# Connectors.net
KiCad netlist of a schematic drawn in Altium Designer
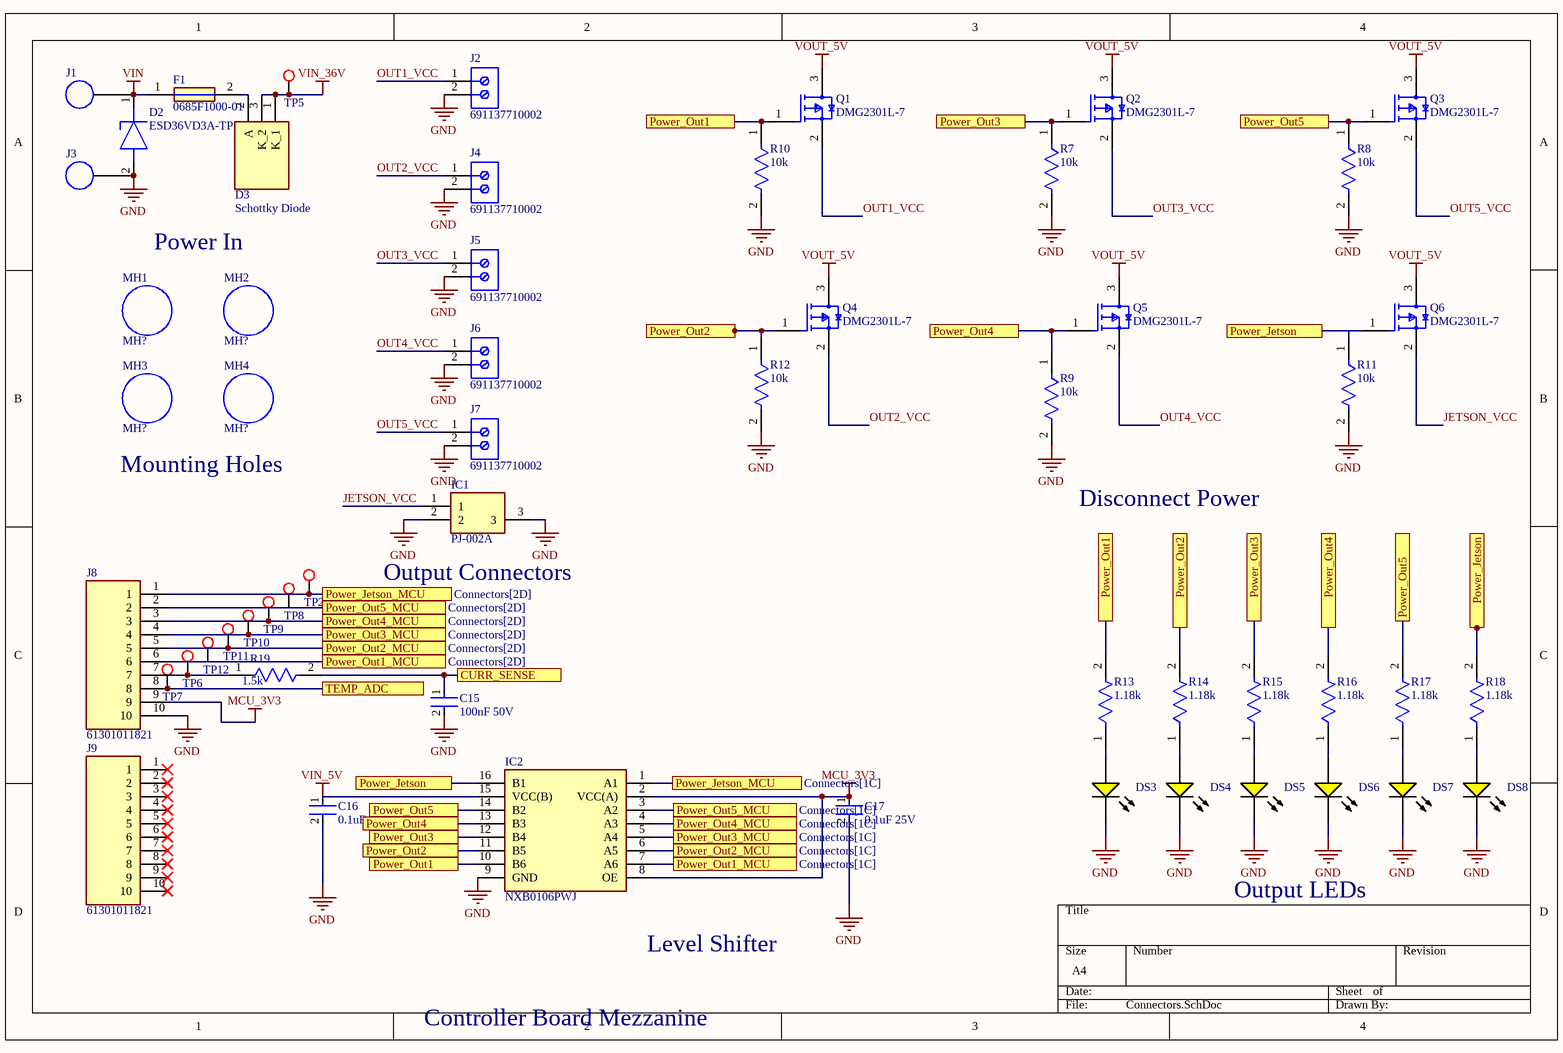
[diagram p0: Connectors.SchDoc]

(export (version "E")
  (design (tool "Eeschema 10.0.6"))
  (components
    (comp (ref "C15")
      (value "100nF 50V")
      (footprint "FP-CL31-IPC_C")
      (description "Cap Ceramic 100nF 50V X7R ±10% SMD 1206 +125°C Embossed T/R")
      (fields (field (name "TOLERANCE") "10%"))
      (libsource (lib "Altium Content Vault") (part "b4654b650e69147ec39a6b967a45e02"))
    )
    (comp (ref "C16")
      (value "0.1uF 25V")
      (footprint "FP-CL21-IPC_C")
      (description "CL21 Series 0805 100nF 25V -20/+80% Tolerance Y5V Multilayer Ceramic Chip Capacitor")
      (fields (field (name "TOLERANCE") "80%"))
      (libsource (lib "Altium Content Vault") (part "b4654b650e69147ec39a6b967a45e02"))
    )
    (comp (ref "C17")
      (value "0.1uF 25V")
      (footprint "FP-CL21-IPC_C")
      (description "CL21 Series 0805 100nF 25V -20/+80% Tolerance Y5V Multilayer Ceramic Chip Capacitor")
      (fields (field (name "TOLERANCE") "80%"))
      (libsource (lib "Altium Content Vault") (part "b4654b650e69147ec39a6b967a45e02"))
    )
    (comp (ref "D2")
      (value "ESD36VD3A-TP")
      (footprint "SamacSys:SOD2512X115N")
      (description "Diode ESD (Uni-directional)")
      (libsource (lib "*") (part "ESD36VD3A-TP"))
    )
    (comp (ref "D3")
      (value "Schottky Diode")
      (footprint "SamacSys:PMEG4010EXEX")
      (fields (field (name "MANUFACTURER_PART_NUMBER") "PMEG6010EXEX"))
      (libsource (lib "*") (part "PMEG6010EXEX"))
    )
    (comp (ref "DS3")
      (value "HSMY-C190")
      (footprint "AVAG-HSMX-C190_V")
      (description "LED Uni-Color Yellow, 65 mW, 20 mA, -40 to 85 degC, 2-Pin SMD, RoHS, Tape and Reel")
      (fields (field (name "TOLERANCE") "1%"))
      (libsource (lib "Altium Content Vault") (part "LED-YELLOW-AK-2"))
    )
    (comp (ref "DS4")
      (value "HSMY-C190")
      (footprint "AVAG-HSMX-C190_V")
      (description "LED Uni-Color Yellow, 65 mW, 20 mA, -40 to 85 degC, 2-Pin SMD, RoHS, Tape and Reel")
      (fields (field (name "TOLERANCE") "1%"))
      (libsource (lib "Altium Content Vault") (part "LED-YELLOW-AK-2"))
    )
    (comp (ref "DS5")
      (value "HSMY-C190")
      (footprint "AVAG-HSMX-C190_V")
      (description "LED Uni-Color Yellow, 65 mW, 20 mA, -40 to 85 degC, 2-Pin SMD, RoHS, Tape and Reel")
      (fields (field (name "TOLERANCE") "1%"))
      (libsource (lib "Altium Content Vault") (part "LED-YELLOW-AK-2"))
    )
    (comp (ref "DS6")
      (value "HSMY-C190")
      (footprint "AVAG-HSMX-C190_V")
      (description "LED Uni-Color Yellow, 65 mW, 20 mA, -40 to 85 degC, 2-Pin SMD, RoHS, Tape and Reel")
      (fields (field (name "TOLERANCE") "1%"))
      (libsource (lib "Altium Content Vault") (part "LED-YELLOW-AK-2"))
    )
    (comp (ref "DS7")
      (value "HSMY-C190")
      (footprint "AVAG-HSMX-C190_V")
      (description "LED Uni-Color Yellow, 65 mW, 20 mA, -40 to 85 degC, 2-Pin SMD, RoHS, Tape and Reel")
      (fields (field (name "TOLERANCE") "1%"))
      (libsource (lib "Altium Content Vault") (part "LED-YELLOW-AK-2"))
    )
    (comp (ref "DS8")
      (value "HSMY-C190")
      (footprint "AVAG-HSMX-C190_V")
      (description "LED Uni-Color Yellow, 65 mW, 20 mA, -40 to 85 degC, 2-Pin SMD, RoHS, Tape and Reel")
      (fields (field (name "TOLERANCE") "1%"))
      (libsource (lib "Altium Content Vault") (part "LED-YELLOW-AK-2"))
    )
    (comp (ref "F1")
      (value "0685F1000-01")
      (footprint "SamacSys:FUSC3216X83N")
      (description "Fuse")
      (libsource (lib "*") (part "0685F1000-01"))
    )
    (comp (ref "IC1")
      (value "PJ-002A")
      (footprint "SamacSys:PJ002A")
      (description "Integrated Circuit")
      (fields (field (name "MOUSER PART NUMBER") "490-PJ-002A"))
      (libsource (lib "*") (part "PJ-002A"))
    )
    (comp (ref "IC2")
      (value "NXB0106PWJ")
      (footprint "SamacSys:SOP65P640X110-16N")
      (description "Integrated Circuit")
      (fields (field (name "MOUSER PART NUMBER") "771-NXB0106PWJ"))
      (libsource (lib "*") (part "NXB0106PWJ"))
    )
    (comp (ref "J1")
      (value "J?")
      (footprint "Power Screw Terminal")
      (libsource (lib "Schlib1") (part "Screw Connector"))
    )
    (comp (ref "J2")
      (value "691137710002")
      (footprint "691137710002")
      (libsource (lib "Altium Content Vault") (part "TBL - 1R - 02P - Screw"))
    )
    (comp (ref "J3")
      (value "J?")
      (footprint "Power Screw Terminal")
      (libsource (lib "Schlib1") (part "Screw Connector"))
    )
    (comp (ref "J4")
      (value "691137710002")
      (footprint "691137710002")
      (libsource (lib "Altium Content Vault") (part "TBL - 1R - 02P - Screw"))
    )
    (comp (ref "J5")
      (value "691137710002")
      (footprint "691137710002")
      (libsource (lib "Altium Content Vault") (part "TBL - 1R - 02P - Screw"))
    )
    (comp (ref "J6")
      (value "691137710002")
      (footprint "691137710002")
      (libsource (lib "Altium Content Vault") (part "TBL - 1R - 02P - Screw"))
    )
    (comp (ref "J7")
      (value "691137710002")
      (footprint "691137710002")
      (libsource (lib "Altium Content Vault") (part "TBL - 1R - 02P - Screw"))
    )
    (comp (ref "J8")
      (value "61301011821")
      (footprint "SamacSys:RHDR10W60P0X254_1X10_2590X250X850P")
      (description "Connector")
      (fields (field (name "MOUSER PART NUMBER") "710-61301011821"))
      (libsource (lib "*") (part "61301011821"))
    )
    (comp (ref "J9")
      (value "61301011821")
      (footprint "SamacSys:RHDR10W60P0X254_1X10_2590X250X850P")
      (description "Connector")
      (fields (field (name "MOUSER PART NUMBER") "710-61301011821"))
      (libsource (lib "*") (part "61301011821"))
    )
    (comp (ref "MH1")
      (value "MH?")
      (footprint "Mounting Hole")
      (libsource (lib "Schlib1") (part "Mounting Hole"))
    )
    (comp (ref "MH2")
      (value "MH?")
      (footprint "Mounting Hole")
      (libsource (lib "Schlib1") (part "Mounting Hole"))
    )
    (comp (ref "MH3")
      (value "MH?")
      (footprint "Mounting Hole")
      (libsource (lib "Schlib1") (part "Mounting Hole"))
    )
    (comp (ref "MH4")
      (value "MH?")
      (footprint "Mounting Hole")
      (libsource (lib "Schlib1") (part "Mounting Hole"))
    )
    (comp (ref "Q1")
      (value "DMG2301L-7")
      (footprint "FP-SOT23-MFG")
      (description "MOSFET P-CH 20V 3A SOT23")
      (fields
        (field (name "MANUFACTURER") "Diodes Inc.")
        (field (name "OCTOPART") "https://octopart.com/dmg2301l-7-diodes+inc.-67250456")
      )
      (libsource (lib "Altium Content Vault") (part "b8f99f9e586195791e7fb11725ebaeb"))
    )
    (comp (ref "Q2")
      (value "DMG2301L-7")
      (footprint "FP-SOT23-MFG")
      (description "MOSFET P-CH 20V 3A SOT23")
      (fields
        (field (name "MANUFACTURER") "Diodes Inc.")
        (field (name "OCTOPART") "https://octopart.com/dmg2301l-7-diodes+inc.-67250456")
      )
      (libsource (lib "Altium Content Vault") (part "b8f99f9e586195791e7fb11725ebaeb"))
    )
    (comp (ref "Q3")
      (value "DMG2301L-7")
      (footprint "FP-SOT23-MFG")
      (description "MOSFET P-CH 20V 3A SOT23")
      (fields
        (field (name "MANUFACTURER") "Diodes Inc.")
        (field (name "OCTOPART") "https://octopart.com/dmg2301l-7-diodes+inc.-67250456")
      )
      (libsource (lib "Altium Content Vault") (part "b8f99f9e586195791e7fb11725ebaeb"))
    )
    (comp (ref "Q4")
      (value "DMG2301L-7")
      (footprint "FP-SOT23-MFG")
      (description "MOSFET P-CH 20V 3A SOT23")
      (fields
        (field (name "MANUFACTURER") "Diodes Inc.")
        (field (name "OCTOPART") "https://octopart.com/dmg2301l-7-diodes+inc.-67250456")
      )
      (libsource (lib "Altium Content Vault") (part "b8f99f9e586195791e7fb11725ebaeb"))
    )
    (comp (ref "Q5")
      (value "DMG2301L-7")
      (footprint "FP-SOT23-MFG")
      (description "MOSFET P-CH 20V 3A SOT23")
      (fields
        (field (name "MANUFACTURER") "Diodes Inc.")
        (field (name "OCTOPART") "https://octopart.com/dmg2301l-7-diodes+inc.-67250456")
      )
      (libsource (lib "Altium Content Vault") (part "b8f99f9e586195791e7fb11725ebaeb"))
    )
    (comp (ref "Q6")
      (value "DMG2301L-7")
      (footprint "FP-SOT23-MFG")
      (description "MOSFET P-CH 20V 3A SOT23")
      (fields
        (field (name "MANUFACTURER") "Diodes Inc.")
        (field (name "OCTOPART") "https://octopart.com/dmg2301l-7-diodes+inc.-67250456")
      )
      (libsource (lib "Altium Content Vault") (part "b8f99f9e586195791e7fb11725ebaeb"))
    )
    (comp (ref "R7")
      (value "10k")
      (footprint "FP-MC01W0805-IPC_C")
      (description "Resistor, 10K, 0.1W, 1%, 0805, Reel")
      (fields (field (name "TOLERANCE") "1%"))
      (libsource (lib "Altium Content Vault") (part "1029c3af85768c4190bb7ad29bc67b5"))
    )
    (comp (ref "R8")
      (value "10k")
      (footprint "FP-MC01W0805-IPC_C")
      (description "Resistor, 10K, 0.1W, 1%, 0805, Reel")
      (fields (field (name "TOLERANCE") "1%"))
      (libsource (lib "Altium Content Vault") (part "1029c3af85768c4190bb7ad29bc67b5"))
    )
    (comp (ref "R9")
      (value "10k")
      (footprint "FP-MC01W0805-IPC_C")
      (description "Resistor, 10K, 0.1W, 1%, 0805, Reel")
      (fields (field (name "TOLERANCE") "1%"))
      (libsource (lib "Altium Content Vault") (part "1029c3af85768c4190bb7ad29bc67b5"))
    )
    (comp (ref "R10")
      (value "10k")
      (footprint "FP-MC01W0805-IPC_C")
      (description "Resistor, 10K, 0.1W, 1%, 0805, Reel")
      (fields (field (name "TOLERANCE") "1%"))
      (libsource (lib "Altium Content Vault") (part "1029c3af85768c4190bb7ad29bc67b5"))
    )
    (comp (ref "R11")
      (value "10k")
      (footprint "FP-MC01W0805-IPC_C")
      (description "Resistor, 10K, 0.1W, 1%, 0805, Reel")
      (fields (field (name "TOLERANCE") "1%"))
      (libsource (lib "Altium Content Vault") (part "1029c3af85768c4190bb7ad29bc67b5"))
    )
    (comp (ref "R12")
      (value "10k")
      (footprint "FP-MC01W0805-IPC_C")
      (description "Resistor, 10K, 0.1W, 1%, 0805, Reel")
      (fields (field (name "TOLERANCE") "1%"))
      (libsource (lib "Altium Content Vault") (part "1029c3af85768c4190bb7ad29bc67b5"))
    )
    (comp (ref "R13")
      (value "1.18k")
      (footprint "FP-CPF0603-MFG")
      (description "RES SMD 1.18KΩ 1% 1/16W 0603")
      (fields
        (field (name "OCTOPART") "https://octopart.com/cpf0603f1k18c1-te+connectivity-7514649")
        (field (name "MANUFACTURER") "TE Connectivity")
      )
      (libsource (lib "Altium Content Vault") (part "1029c3af85768c4190bb7ad29bc67b5"))
    )
    (comp (ref "R14")
      (value "1.18k")
      (footprint "FP-CPF0603-MFG")
      (description "RES SMD 1.18KΩ 1% 1/16W 0603")
      (fields
        (field (name "OCTOPART") "https://octopart.com/cpf0603f1k18c1-te+connectivity-7514649")
        (field (name "MANUFACTURER") "TE Connectivity")
      )
      (libsource (lib "Altium Content Vault") (part "1029c3af85768c4190bb7ad29bc67b5"))
    )
    (comp (ref "R15")
      (value "1.18k")
      (footprint "FP-CPF0603-MFG")
      (description "RES SMD 1.18KΩ 1% 1/16W 0603")
      (fields
        (field (name "OCTOPART") "https://octopart.com/cpf0603f1k18c1-te+connectivity-7514649")
        (field (name "MANUFACTURER") "TE Connectivity")
      )
      (libsource (lib "Altium Content Vault") (part "1029c3af85768c4190bb7ad29bc67b5"))
    )
    (comp (ref "R16")
      (value "1.18k")
      (footprint "FP-CPF0603-MFG")
      (description "RES SMD 1.18KΩ 1% 1/16W 0603")
      (fields
        (field (name "OCTOPART") "https://octopart.com/cpf0603f1k18c1-te+connectivity-7514649")
        (field (name "MANUFACTURER") "TE Connectivity")
      )
      (libsource (lib "Altium Content Vault") (part "1029c3af85768c4190bb7ad29bc67b5"))
    )
    (comp (ref "R17")
      (value "1.18k")
      (footprint "FP-CPF0603-MFG")
      (description "RES SMD 1.18KΩ 1% 1/16W 0603")
      (fields
        (field (name "OCTOPART") "https://octopart.com/cpf0603f1k18c1-te+connectivity-7514649")
        (field (name "MANUFACTURER") "TE Connectivity")
      )
      (libsource (lib "Altium Content Vault") (part "1029c3af85768c4190bb7ad29bc67b5"))
    )
    (comp (ref "R18")
      (value "1.18k")
      (footprint "FP-CPF0603-MFG")
      (description "RES SMD 1.18KΩ 1% 1/16W 0603")
      (fields
        (field (name "OCTOPART") "https://octopart.com/cpf0603f1k18c1-te+connectivity-7514649")
        (field (name "MANUFACTURER") "TE Connectivity")
      )
      (libsource (lib "Altium Content Vault") (part "1029c3af85768c4190bb7ad29bc67b5"))
    )
    (comp (ref "R19")
      (value "1.5k")
      (footprint "FP-CRCW0603-e3-IPC_A")
      (description "RES Thick Film, 1.5kΩ, 1%, 0.1W, 100ppm/°C, 0603")
      (fields (field (name "TOLERANCE") "1%"))
      (libsource (lib "Altium Content Vault") (part "1029c3af85768c4190bb7ad29bc67b5"))
    )
    (comp (ref "TP2") (value "TP") (footprint "Testpoint") (libsource (lib "Schlib1") (part "Testpoint")))
    (comp (ref "TP5") (value "TP") (footprint "Testpoint") (libsource (lib "Schlib1") (part "Testpoint")))
    (comp (ref "TP6") (value "TP") (footprint "Testpoint") (libsource (lib "Schlib1") (part "Testpoint")))
    (comp (ref "TP7") (value "TP") (footprint "Testpoint") (libsource (lib "Schlib1") (part "Testpoint")))
    (comp (ref "TP8") (value "TP") (footprint "Testpoint") (libsource (lib "Schlib1") (part "Testpoint")))
    (comp (ref "TP9") (value "TP") (footprint "Testpoint") (libsource (lib "Schlib1") (part "Testpoint")))
    (comp (ref "TP10") (value "TP") (footprint "Testpoint") (libsource (lib "Schlib1") (part "Testpoint")))
    (comp (ref "TP11") (value "TP") (footprint "Testpoint") (libsource (lib "Schlib1") (part "Testpoint")))
    (comp (ref "TP12") (value "TP") (footprint "Testpoint") (libsource (lib "Schlib1") (part "Testpoint")))
  )
  (nets
    (net (code "1") (name "/CURR_SENSE") (class "Default")
      (node (ref "C15") (pin "1") (pinfunction "1_1") (pintype "passive"))
      (node (ref "R19") (pin "2") (pinfunction "2_2") (pintype "passive"))
    )
    (net (code "2") (name "/JETSON_VCC") (class "Default")
      (node (ref "IC1") (pin "1") (pinfunction "1_1") (pintype "passive"))
      (node (ref "Q6") (pin "2") (pinfunction "S_2") (pintype "passive"))
    )
    (net (code "3") (name "/OUT1_VCC") (class "Default")
      (node (ref "J2") (pin "1") (pinfunction "1_1") (pintype "passive"))
      (node (ref "Q1") (pin "2") (pinfunction "S_2") (pintype "passive"))
    )
    (net (code "4") (name "/OUT2_VCC") (class "Default")
      (node (ref "J4") (pin "1") (pinfunction "1_1") (pintype "passive"))
      (node (ref "Q4") (pin "2") (pinfunction "S_2") (pintype "passive"))
    )
    (net (code "5") (name "/OUT3_VCC") (class "Default")
      (node (ref "J5") (pin "1") (pinfunction "1_1") (pintype "passive"))
      (node (ref "Q2") (pin "2") (pinfunction "S_2") (pintype "passive"))
    )
    (net (code "6") (name "/OUT4_VCC") (class "Default")
      (node (ref "J6") (pin "1") (pinfunction "1_1") (pintype "passive"))
      (node (ref "Q5") (pin "2") (pinfunction "S_2") (pintype "passive"))
    )
    (net (code "7") (name "/OUT5_VCC") (class "Default")
      (node (ref "J7") (pin "1") (pinfunction "1_1") (pintype "passive"))
      (node (ref "Q3") (pin "2") (pinfunction "S_2") (pintype "passive"))
    )
    (net (code "8") (name "/Power_Jetson") (class "Default")
      (node (ref "IC2") (pin "16") (pinfunction "B1_16") (pintype "passive"))
      (node (ref "Q6") (pin "1") (pinfunction "G_1") (pintype "passive"))
      (node (ref "R11") (pin "1") (pinfunction "1_1") (pintype "passive"))
      (node (ref "R18") (pin "2") (pinfunction "2_2") (pintype "passive"))
    )
    (net (code "9") (name "/Power_Jetson_MCU") (class "Default")
      (node (ref "IC2") (pin "1") (pinfunction "A1_1") (pintype "passive"))
      (node (ref "J8") (pin "1") (pinfunction "1_1") (pintype "passive"))
      (node (ref "TP2") (pin "0") (pinfunction "0_0") (pintype "passive"))
    )
    (net (code "10") (name "/Power_Out1") (class "Default")
      (node (ref "IC2") (pin "10") (pinfunction "B6_10") (pintype "passive"))
      (node (ref "Q1") (pin "1") (pinfunction "G_1") (pintype "passive"))
      (node (ref "R10") (pin "1") (pinfunction "1_1") (pintype "passive"))
      (node (ref "R13") (pin "2") (pinfunction "2_2") (pintype "passive"))
    )
    (net (code "11") (name "/Power_Out1_MCU") (class "Default")
      (node (ref "IC2") (pin "7") (pinfunction "A6_7") (pintype "passive"))
      (node (ref "J8") (pin "6") (pinfunction "6_6") (pintype "passive"))
      (node (ref "TP12") (pin "0") (pinfunction "0_0") (pintype "passive"))
    )
    (net (code "12") (name "/Power_Out2") (class "Default")
      (node (ref "IC2") (pin "11") (pinfunction "B5_11") (pintype "passive"))
      (node (ref "Q4") (pin "1") (pinfunction "G_1") (pintype "passive"))
      (node (ref "R12") (pin "1") (pinfunction "1_1") (pintype "passive"))
      (node (ref "R14") (pin "2") (pinfunction "2_2") (pintype "passive"))
    )
    (net (code "13") (name "/Power_Out2_MCU") (class "Default")
      (node (ref "IC2") (pin "6") (pinfunction "A5_6") (pintype "passive"))
      (node (ref "J8") (pin "5") (pinfunction "5_5") (pintype "passive"))
      (node (ref "TP11") (pin "0") (pinfunction "0_0") (pintype "passive"))
    )
    (net (code "14") (name "/Power_Out3") (class "Default")
      (node (ref "IC2") (pin "12") (pinfunction "B4_12") (pintype "passive"))
      (node (ref "Q2") (pin "1") (pinfunction "G_1") (pintype "passive"))
      (node (ref "R15") (pin "2") (pinfunction "2_2") (pintype "passive"))
      (node (ref "R7") (pin "1") (pinfunction "1_1") (pintype "passive"))
    )
    (net (code "15") (name "/Power_Out3_MCU") (class "Default")
      (node (ref "IC2") (pin "5") (pinfunction "A4_5") (pintype "passive"))
      (node (ref "J8") (pin "4") (pinfunction "4_4") (pintype "passive"))
      (node (ref "TP10") (pin "0") (pinfunction "0_0") (pintype "passive"))
    )
    (net (code "16") (name "/Power_Out4") (class "Default")
      (node (ref "IC2") (pin "13") (pinfunction "B3_13") (pintype "passive"))
      (node (ref "Q5") (pin "1") (pinfunction "G_1") (pintype "passive"))
      (node (ref "R16") (pin "2") (pinfunction "2_2") (pintype "passive"))
      (node (ref "R9") (pin "1") (pinfunction "1_1") (pintype "passive"))
    )
    (net (code "17") (name "/Power_Out4_MCU") (class "Default")
      (node (ref "IC2") (pin "4") (pinfunction "A3_4") (pintype "passive"))
      (node (ref "J8") (pin "3") (pinfunction "3_3") (pintype "passive"))
      (node (ref "TP9") (pin "0") (pinfunction "0_0") (pintype "passive"))
    )
    (net (code "18") (name "/Power_Out5") (class "Default")
      (node (ref "IC2") (pin "14") (pinfunction "B2_14") (pintype "passive"))
      (node (ref "Q3") (pin "1") (pinfunction "G_1") (pintype "passive"))
      (node (ref "R17") (pin "2") (pinfunction "2_2") (pintype "passive"))
      (node (ref "R8") (pin "1") (pinfunction "1_1") (pintype "passive"))
    )
    (net (code "19") (name "/Power_Out5_MCU") (class "Default")
      (node (ref "IC2") (pin "3") (pinfunction "A2_3") (pintype "passive"))
      (node (ref "J8") (pin "2") (pinfunction "2_2") (pintype "passive"))
      (node (ref "TP8") (pin "0") (pinfunction "0_0") (pintype "passive"))
    )
    (net (code "20") (name "/TEMP_ADC") (class "Default")
      (node (ref "J8") (pin "8") (pinfunction "8_8") (pintype "passive"))
      (node (ref "TP7") (pin "0") (pinfunction "0_0") (pintype "passive"))
    )
    (net (code "21") (name "GND") (class "Default")
      (node (ref "C15") (pin "2") (pinfunction "2_2") (pintype "passive"))
      (node (ref "C16") (pin "2") (pinfunction "2_2") (pintype "passive"))
      (node (ref "C17") (pin "2") (pinfunction "2_2") (pintype "passive"))
      (node (ref "D2") (pin "2") (pinfunction "A_2") (pintype "passive"))
      (node (ref "DS3") (pin "2") (pinfunction "K_2") (pintype "passive"))
      (node (ref "DS4") (pin "2") (pinfunction "K_2") (pintype "passive"))
      (node (ref "DS5") (pin "2") (pinfunction "K_2") (pintype "passive"))
      (node (ref "DS6") (pin "2") (pinfunction "K_2") (pintype "passive"))
      (node (ref "DS7") (pin "2") (pinfunction "K_2") (pintype "passive"))
      (node (ref "DS8") (pin "2") (pinfunction "K_2") (pintype "passive"))
      (node (ref "IC1") (pin "2") (pinfunction "2_2") (pintype "passive"))
      (node (ref "IC1") (pin "3") (pinfunction "3_3") (pintype "passive"))
      (node (ref "IC2") (pin "9") (pinfunction "GND_9") (pintype "passive"))
      (node (ref "J2") (pin "2") (pinfunction "2_2") (pintype "passive"))
      (node (ref "J3") (pin "1") (pinfunction "1_1") (pintype "passive"))
      (node (ref "J4") (pin "2") (pinfunction "2_2") (pintype "passive"))
      (node (ref "J5") (pin "2") (pinfunction "2_2") (pintype "passive"))
      (node (ref "J6") (pin "2") (pinfunction "2_2") (pintype "passive"))
      (node (ref "J7") (pin "2") (pinfunction "2_2") (pintype "passive"))
      (node (ref "J8") (pin "10") (pinfunction "10_10") (pintype "passive"))
      (node (ref "R10") (pin "2") (pinfunction "2_2") (pintype "passive"))
      (node (ref "R11") (pin "2") (pinfunction "2_2") (pintype "passive"))
      (node (ref "R12") (pin "2") (pinfunction "2_2") (pintype "passive"))
      (node (ref "R7") (pin "2") (pinfunction "2_2") (pintype "passive"))
      (node (ref "R8") (pin "2") (pinfunction "2_2") (pintype "passive"))
      (node (ref "R9") (pin "2") (pinfunction "2_2") (pintype "passive"))
    )
    (net (code "22") (name "MCU_3V3") (class "Default")
      (node (ref "C17") (pin "1") (pinfunction "1_1") (pintype "passive"))
      (node (ref "IC2") (pin "2") (pinfunction "VCC(A)_2") (pintype "passive"))
      (node (ref "IC2") (pin "8") (pinfunction "OE_8") (pintype "passive"))
      (node (ref "J8") (pin "9") (pinfunction "9_9") (pintype "passive"))
    )
    (net (code "23") (name "Net-(D3-A)") (class "Default")
      (node (ref "D3") (pin "2") (pinfunction "A_2") (pintype "passive"))
      (node (ref "F1") (pin "2") (pinfunction "2_2") (pintype "passive"))
    )
    (net (code "24") (name "Net-(DS3-A)") (class "Default")
      (node (ref "DS3") (pin "1") (pinfunction "A_1") (pintype "passive"))
      (node (ref "R13") (pin "1") (pinfunction "1_1") (pintype "passive"))
    )
    (net (code "25") (name "Net-(DS4-A)") (class "Default")
      (node (ref "DS4") (pin "1") (pinfunction "A_1") (pintype "passive"))
      (node (ref "R14") (pin "1") (pinfunction "1_1") (pintype "passive"))
    )
    (net (code "26") (name "Net-(DS5-A)") (class "Default")
      (node (ref "DS5") (pin "1") (pinfunction "A_1") (pintype "passive"))
      (node (ref "R15") (pin "1") (pinfunction "1_1") (pintype "passive"))
    )
    (net (code "27") (name "Net-(DS6-A)") (class "Default")
      (node (ref "DS6") (pin "1") (pinfunction "A_1") (pintype "passive"))
      (node (ref "R16") (pin "1") (pinfunction "1_1") (pintype "passive"))
    )
    (net (code "28") (name "Net-(DS7-A)") (class "Default")
      (node (ref "DS7") (pin "1") (pinfunction "A_1") (pintype "passive"))
      (node (ref "R17") (pin "1") (pinfunction "1_1") (pintype "passive"))
    )
    (net (code "29") (name "Net-(DS8-A)") (class "Default")
      (node (ref "DS8") (pin "1") (pinfunction "A_1") (pintype "passive"))
      (node (ref "R18") (pin "1") (pinfunction "1_1") (pintype "passive"))
    )
    (net (code "30") (name "Net-(J8-Pad7)") (class "Default")
      (node (ref "J8") (pin "7") (pinfunction "7_7") (pintype "passive"))
      (node (ref "R19") (pin "1") (pinfunction "1_1") (pintype "passive"))
      (node (ref "TP6") (pin "0") (pinfunction "0_0") (pintype "passive"))
    )
    (net (code "31") (name "VIN") (class "Default")
      (node (ref "D2") (pin "1") (pinfunction "K_1") (pintype "passive"))
      (node (ref "F1") (pin "1") (pinfunction "1_1") (pintype "passive"))
      (node (ref "J1") (pin "1") (pinfunction "1_1") (pintype "passive"))
    )
    (net (code "32") (name "VIN_5V") (class "Default")
      (node (ref "C16") (pin "1") (pinfunction "1_1") (pintype "passive"))
      (node (ref "IC2") (pin "15") (pinfunction "VCC(B)_15") (pintype "passive"))
    )
    (net (code "33") (name "VIN_36V") (class "Default")
      (node (ref "D3") (pin "1") (pinfunction "K_1_1") (pintype "passive"))
      (node (ref "D3") (pin "3") (pinfunction "K_2_3") (pintype "passive"))
      (node (ref "TP5") (pin "0") (pinfunction "0_0") (pintype "passive"))
    )
    (net (code "34") (name "VOUT_5V") (class "Default")
      (node (ref "Q1") (pin "3") (pinfunction "D_3") (pintype "passive"))
      (node (ref "Q2") (pin "3") (pinfunction "D_3") (pintype "passive"))
      (node (ref "Q3") (pin "3") (pinfunction "D_3") (pintype "passive"))
      (node (ref "Q4") (pin "3") (pinfunction "D_3") (pintype "passive"))
      (node (ref "Q5") (pin "3") (pinfunction "D_3") (pintype "passive"))
      (node (ref "Q6") (pin "3") (pinfunction "D_3") (pintype "passive"))
    )
    (net (code "35") (name "unconnected-(J9-Pad1)") (class "Default")
      (node (ref "J9") (pin "1") (pinfunction "1_1") (pintype "passive+no_connect"))
    )
    (net (code "36") (name "unconnected-(J9-Pad2)") (class "Default")
      (node (ref "J9") (pin "2") (pinfunction "2_2") (pintype "passive+no_connect"))
    )
    (net (code "37") (name "unconnected-(J9-Pad3)") (class "Default")
      (node (ref "J9") (pin "3") (pinfunction "3_3") (pintype "passive+no_connect"))
    )
    (net (code "38") (name "unconnected-(J9-Pad4)") (class "Default")
      (node (ref "J9") (pin "4") (pinfunction "4_4") (pintype "passive+no_connect"))
    )
    (net (code "39") (name "unconnected-(J9-Pad5)") (class "Default")
      (node (ref "J9") (pin "5") (pinfunction "5_5") (pintype "passive+no_connect"))
    )
    (net (code "40") (name "unconnected-(J9-Pad6)") (class "Default")
      (node (ref "J9") (pin "6") (pinfunction "6_6") (pintype "passive+no_connect"))
    )
    (net (code "41") (name "unconnected-(J9-Pad7)") (class "Default")
      (node (ref "J9") (pin "7") (pinfunction "7_7") (pintype "passive+no_connect"))
    )
    (net (code "42") (name "unconnected-(J9-Pad8)") (class "Default")
      (node (ref "J9") (pin "8") (pinfunction "8_8") (pintype "passive+no_connect"))
    )
    (net (code "43") (name "unconnected-(J9-Pad9)") (class "Default")
      (node (ref "J9") (pin "9") (pinfunction "9_9") (pintype "passive+no_connect"))
    )
    (net (code "44") (name "unconnected-(J9-Pad10)") (class "Default")
      (node (ref "J9") (pin "10") (pinfunction "10_10") (pintype "passive+no_connect"))
    )
  )
)
